# qsop28_to_dip.net
KiCad netlist of a schematic drawn in EAGLE
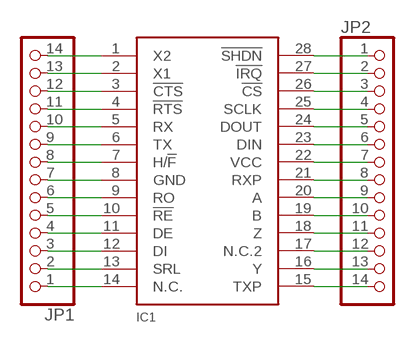
[diagram p0: schematic, sheet 1]

(export (version "E")
  (design (tool "Eeschema 10.0.6"))
  (components
    (comp (ref "IC1")
      (value "MAX314028SQSOP")
      (footprint "eagle-import:28QSOP")
      (libsource (lib "eagle-import") (part "MAX314028SQSOP"))
    )
    (comp (ref "JP1")
      (value "PINHD-1X14")
      (footprint "eagle-import:1X14")
      (libsource (lib "eagle-import") (part "PINHD-1X14"))
    )
    (comp (ref "JP2")
      (value "PINHD-1X14")
      (footprint "eagle-import:1X14")
      (libsource (lib "eagle-import") (part "PINHD-1X14"))
    )
  )
  (nets
    (net (code "1") (name "Net-(IC1-A)") (class "Default")
      (node (ref "IC1") (pin "20") (pinfunction "A_20") (pintype "bidirectional"))
      (node (ref "JP2") (pin "9") (pinfunction "9_9") (pintype "passive"))
    )
    (net (code "2") (name "Net-(IC1-B)") (class "Default")
      (node (ref "IC1") (pin "19") (pinfunction "B_19") (pintype "bidirectional"))
      (node (ref "JP2") (pin "10") (pinfunction "10_10") (pintype "passive"))
    )
    (net (code "3") (name "Net-(IC1-DE)") (class "Default")
      (node (ref "IC1") (pin "11") (pinfunction "DE_11") (pintype "bidirectional"))
      (node (ref "JP1") (pin "4") (pinfunction "4_4") (pintype "passive"))
    )
    (net (code "4") (name "Net-(IC1-DI)") (class "Default")
      (node (ref "IC1") (pin "12") (pinfunction "DI_12") (pintype "bidirectional"))
      (node (ref "JP1") (pin "3") (pinfunction "3_3") (pintype "passive"))
    )
    (net (code "5") (name "Net-(IC1-DIN)") (class "Default")
      (node (ref "IC1") (pin "23") (pinfunction "DIN_23") (pintype "bidirectional"))
      (node (ref "JP2") (pin "6") (pinfunction "6_6") (pintype "passive"))
    )
    (net (code "6") (name "Net-(IC1-DOUT)") (class "Default")
      (node (ref "IC1") (pin "24") (pinfunction "DOUT_24") (pintype "bidirectional"))
      (node (ref "JP2") (pin "5") (pinfunction "5_5") (pintype "passive"))
    )
    (net (code "7") (name "Net-(IC1-GND)") (class "Default")
      (node (ref "IC1") (pin "8") (pinfunction "GND_8") (pintype "bidirectional"))
      (node (ref "JP1") (pin "7") (pinfunction "7_7") (pintype "passive"))
    )
    (net (code "8") (name "Net-(IC1-H{slash}~{F})") (class "Default")
      (node (ref "IC1") (pin "7") (pinfunction "H/~{F}_7") (pintype "bidirectional"))
      (node (ref "JP1") (pin "8") (pinfunction "8_8") (pintype "passive"))
    )
    (net (code "9") (name "Net-(IC1-N.C.)") (class "Default")
      (node (ref "IC1") (pin "14") (pinfunction "N.C._14") (pintype "bidirectional"))
      (node (ref "JP1") (pin "1") (pinfunction "1_1") (pintype "passive"))
    )
    (net (code "10") (name "Net-(IC1-N.C.2)") (class "Default")
      (node (ref "IC1") (pin "17") (pinfunction "N.C.2_17") (pintype "bidirectional"))
      (node (ref "JP2") (pin "12") (pinfunction "12_12") (pintype "passive"))
    )
    (net (code "11") (name "Net-(IC1-RO)") (class "Default")
      (node (ref "IC1") (pin "9") (pinfunction "RO_9") (pintype "bidirectional"))
      (node (ref "JP1") (pin "6") (pinfunction "6_6") (pintype "passive"))
    )
    (net (code "12") (name "Net-(IC1-RX)") (class "Default")
      (node (ref "IC1") (pin "5") (pinfunction "RX_5") (pintype "bidirectional"))
      (node (ref "JP1") (pin "10") (pinfunction "10_10") (pintype "passive"))
    )
    (net (code "13") (name "Net-(IC1-RXP)") (class "Default")
      (node (ref "IC1") (pin "21") (pinfunction "RXP_21") (pintype "bidirectional"))
      (node (ref "JP2") (pin "8") (pinfunction "8_8") (pintype "passive"))
    )
    (net (code "14") (name "Net-(IC1-SCLK)") (class "Default")
      (node (ref "IC1") (pin "25") (pinfunction "SCLK_25") (pintype "bidirectional"))
      (node (ref "JP2") (pin "4") (pinfunction "4_4") (pintype "passive"))
    )
    (net (code "15") (name "Net-(IC1-SRL)") (class "Default")
      (node (ref "IC1") (pin "13") (pinfunction "SRL_13") (pintype "bidirectional"))
      (node (ref "JP1") (pin "2") (pinfunction "2_2") (pintype "passive"))
    )
    (net (code "16") (name "Net-(IC1-TX)") (class "Default")
      (node (ref "IC1") (pin "6") (pinfunction "TX_6") (pintype "bidirectional"))
      (node (ref "JP1") (pin "9") (pinfunction "9_9") (pintype "passive"))
    )
    (net (code "17") (name "Net-(IC1-TXP)") (class "Default")
      (node (ref "IC1") (pin "15") (pinfunction "TXP_15") (pintype "bidirectional"))
      (node (ref "JP2") (pin "14") (pinfunction "14_14") (pintype "passive"))
    )
    (net (code "18") (name "Net-(IC1-VCC)") (class "Default")
      (node (ref "IC1") (pin "22") (pinfunction "VCC_22") (pintype "bidirectional"))
      (node (ref "JP2") (pin "7") (pinfunction "7_7") (pintype "passive"))
    )
    (net (code "19") (name "Net-(IC1-X1)") (class "Default")
      (node (ref "IC1") (pin "2") (pinfunction "X1_2") (pintype "bidirectional"))
      (node (ref "JP1") (pin "13") (pinfunction "13_13") (pintype "passive"))
    )
    (net (code "20") (name "Net-(IC1-X2)") (class "Default")
      (node (ref "IC1") (pin "1") (pinfunction "X2_1") (pintype "bidirectional"))
      (node (ref "JP1") (pin "14") (pinfunction "14_14") (pintype "passive"))
    )
    (net (code "21") (name "Net-(IC1-Y)") (class "Default")
      (node (ref "IC1") (pin "16") (pinfunction "Y_16") (pintype "bidirectional"))
      (node (ref "JP2") (pin "13") (pinfunction "13_13") (pintype "passive"))
    )
    (net (code "22") (name "Net-(IC1-Z)") (class "Default")
      (node (ref "IC1") (pin "18") (pinfunction "Z_18") (pintype "bidirectional"))
      (node (ref "JP2") (pin "11") (pinfunction "11_11") (pintype "passive"))
    )
    (net (code "23") (name "Net-(IC1-~{CS})") (class "Default")
      (node (ref "IC1") (pin "26") (pinfunction "~{CS}_26") (pintype "bidirectional"))
      (node (ref "JP2") (pin "3") (pinfunction "3_3") (pintype "passive"))
    )
    (net (code "24") (name "Net-(IC1-~{CTS})") (class "Default")
      (node (ref "IC1") (pin "3") (pinfunction "~{CTS}_3") (pintype "bidirectional"))
      (node (ref "JP1") (pin "12") (pinfunction "12_12") (pintype "passive"))
    )
    (net (code "25") (name "Net-(IC1-~{IRQ})") (class "Default")
      (node (ref "IC1") (pin "27") (pinfunction "~{IRQ}_27") (pintype "bidirectional"))
      (node (ref "JP2") (pin "2") (pinfunction "2_2") (pintype "passive"))
    )
    (net (code "26") (name "Net-(IC1-~{RE})") (class "Default")
      (node (ref "IC1") (pin "10") (pinfunction "~{RE}_10") (pintype "bidirectional"))
      (node (ref "JP1") (pin "5") (pinfunction "5_5") (pintype "passive"))
    )
    (net (code "27") (name "Net-(IC1-~{RTS})") (class "Default")
      (node (ref "IC1") (pin "4") (pinfunction "~{RTS}_4") (pintype "bidirectional"))
      (node (ref "JP1") (pin "11") (pinfunction "11_11") (pintype "passive"))
    )
    (net (code "28") (name "Net-(IC1-~{SHDN})") (class "Default")
      (node (ref "IC1") (pin "28") (pinfunction "~{SHDN}_28") (pintype "bidirectional"))
      (node (ref "JP2") (pin "1") (pinfunction "1_1") (pintype "passive"))
    )
  )
)
